# GNSS_OCXO.net
KiCad netlist of a schematic drawn in Altium Designer
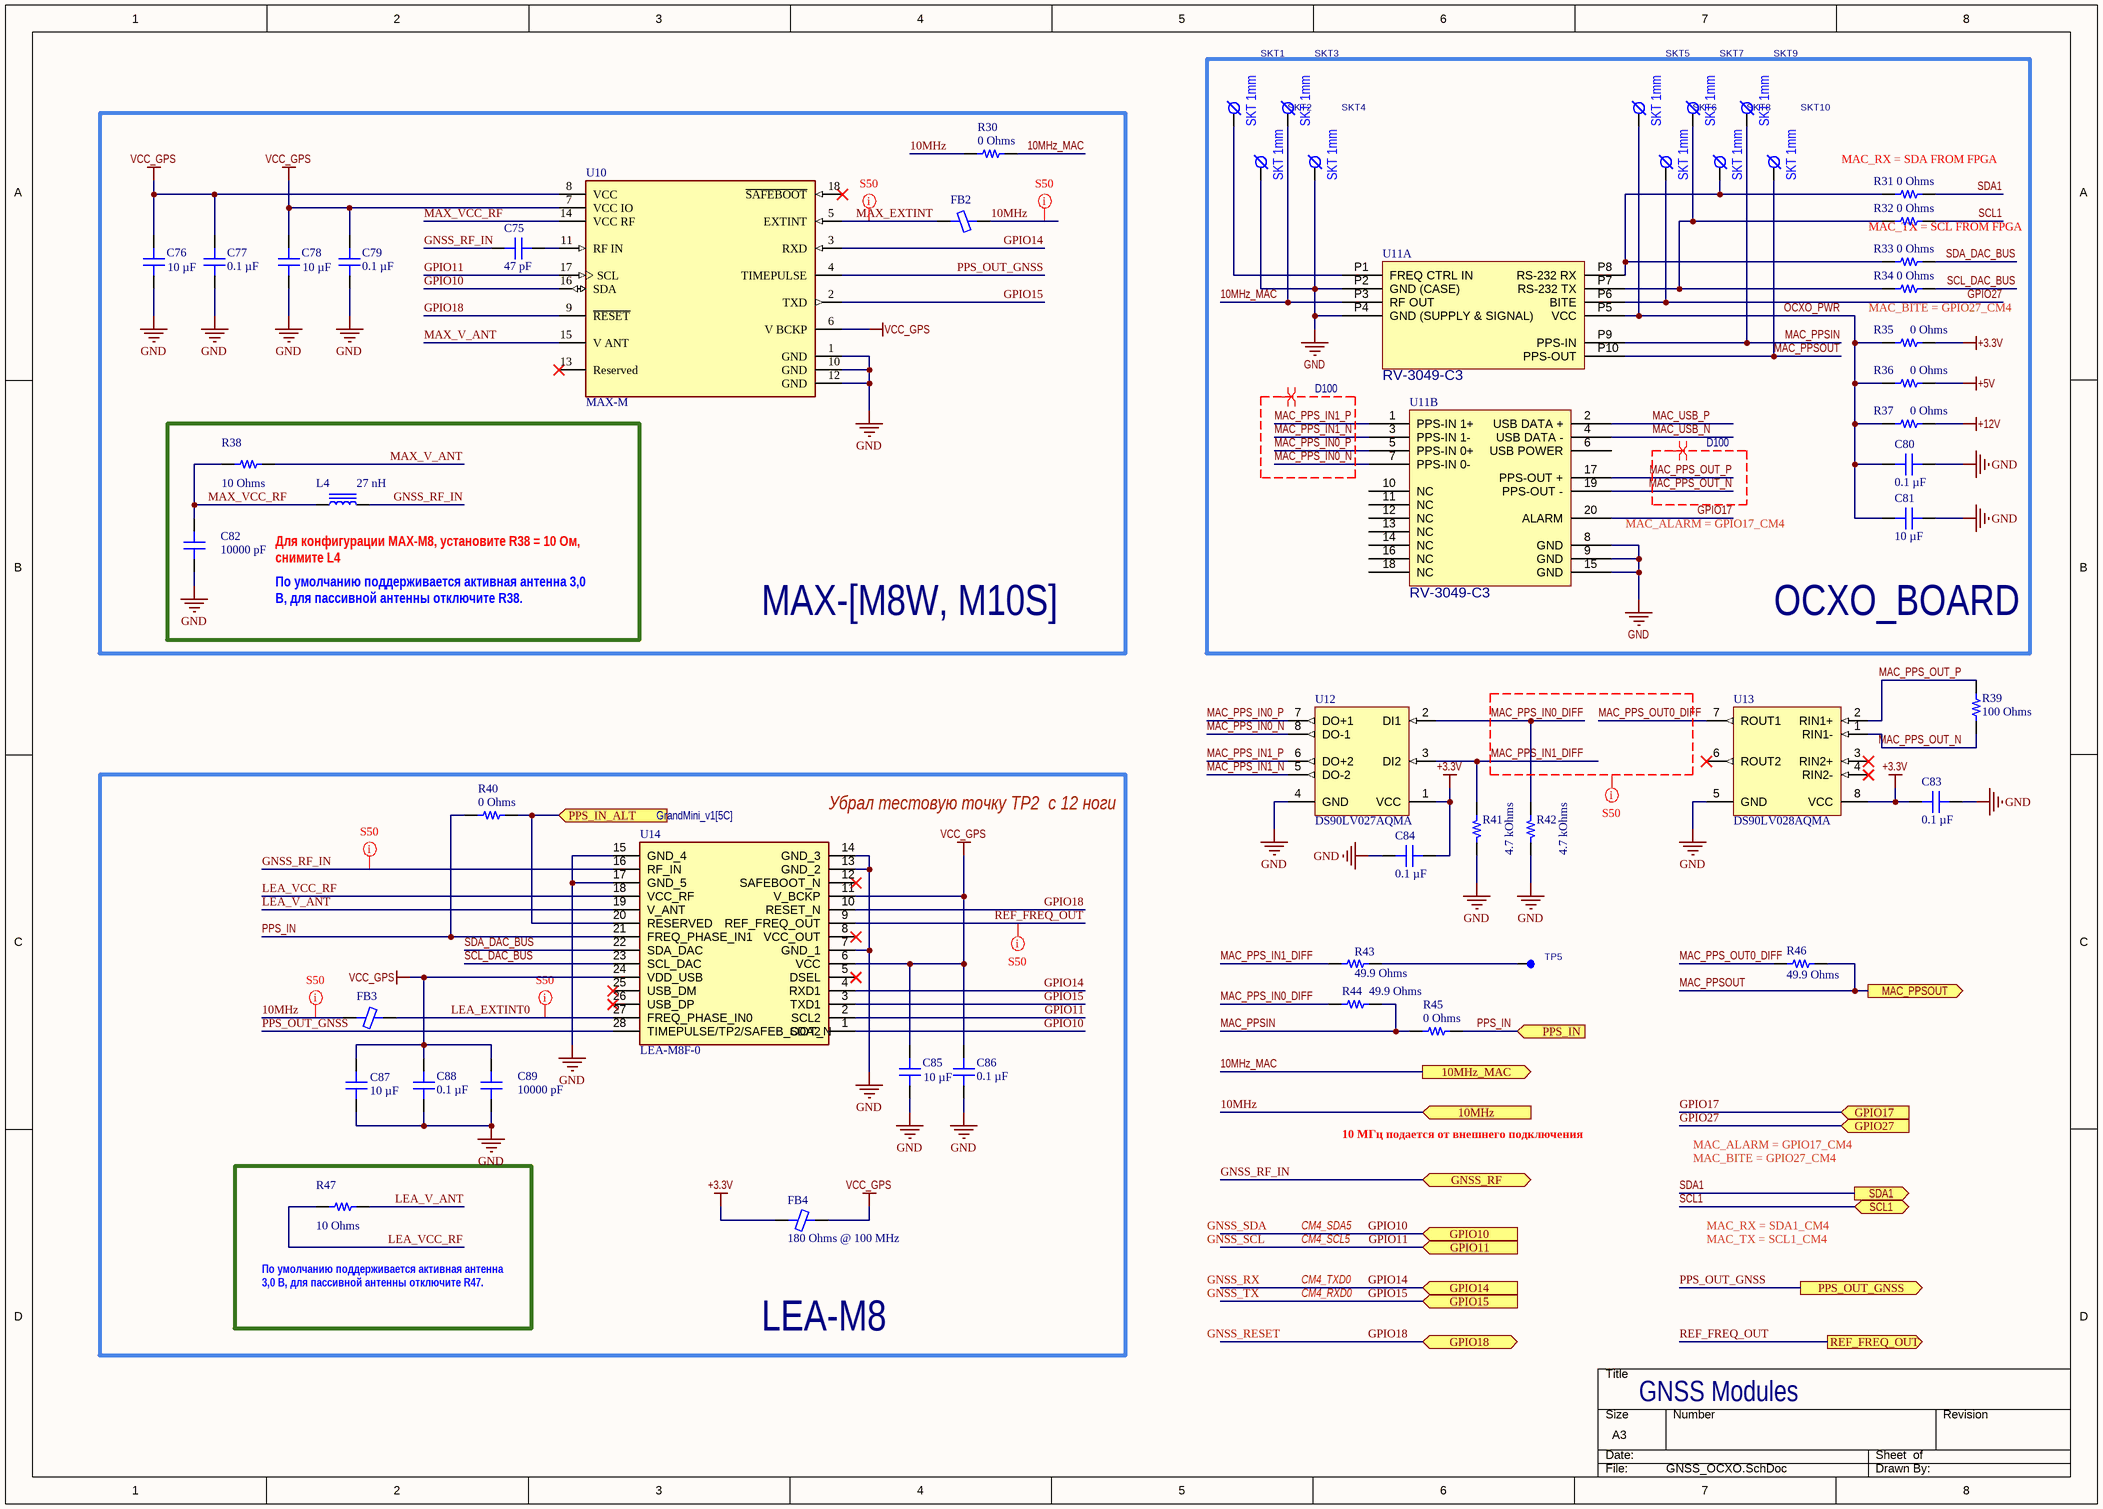
[diagram p0: GNSS_OCXO.SchDoc]

(export (version "E")
  (design (tool "Eeschema 10.0.6"))
  (components
    (comp (ref "C75")
      (value "47 pF")
      (footprint "CAP 0603_1608")
      (description "CAP CER 47PF 25V C0G/NPO 0603")
      (fields (field (name "MANUFACTURER") "Yageo") (field (name "TOLERANCE") "±5%"))
      (libsource (lib "Celestial Altium Library - altium_library") (part "Capacitor"))
    )
    (comp (ref "C76")
      (value "10 µF")
      (footprint "CAP 0805_2012")
      (description "CAP CER 10UF 25V X5R 0805")
      (fields
        (field (name "TOLERANCE") "±10%")
        (field (name "CAPACITANCE") "10 µF")
        (field (name "PART NUMBER") "CC0805KKX5R8BB106")
      )
      (libsource (lib "Celestial Altium Library - altium_library") (part "Capacitor"))
    )
    (comp (ref "C77")
      (value "0.1 µF")
      (footprint "CAP 0603_1608")
      (description "CAP CER 0.1UF 50V X7R 0603")
      (fields (field (name "MANUFACTURER") "Yageo") (field (name "TOLERANCE") "±10%"))
      (libsource (lib "Celestial Altium Library - altium_library") (part "Capacitor"))
    )
    (comp (ref "C78")
      (value "10 µF")
      (footprint "CAP 0805_2012")
      (description "CAP CER 10UF 25V X5R 0805")
      (fields
        (field (name "TOLERANCE") "±10%")
        (field (name "CAPACITANCE") "10 µF")
        (field (name "PART NUMBER") "CC0805KKX5R8BB106")
      )
      (libsource (lib "Celestial Altium Library - altium_library") (part "Capacitor"))
    )
    (comp (ref "C79")
      (value "0.1 µF")
      (footprint "CAP 0603_1608")
      (description "CAP CER 0.1UF 50V X7R 0603")
      (fields (field (name "MANUFACTURER") "Yageo") (field (name "TOLERANCE") "±10%"))
      (libsource (lib "Celestial Altium Library - altium_library") (part "Capacitor"))
    )
    (comp (ref "C80")
      (value "0.1 µF")
      (footprint "CAP 0603_1608")
      (description "CAP CER 0.1UF 50V X7R 0603")
      (fields (field (name "MANUFACTURER") "Yageo") (field (name "PART NUMBER") "CC0603KRX7R9BB104"))
      (libsource (lib "Celestial Altium Library - altium_library") (part "Capacitor"))
    )
    (comp (ref "C81")
      (value "10 µF")
      (footprint "CAP 0805_2012")
      (description "CAP CER 10UF 25V X5R 0805")
      (fields
        (field (name "TOLERANCE") "±10%")
        (field (name "CAPACITANCE") "10 µF")
        (field (name "PART NUMBER") "CC0805KKX5R8BB106")
      )
      (libsource (lib "Celestial Altium Library - altium_library") (part "Capacitor"))
    )
    (comp (ref "C82")
      (value "10000 pF")
      (footprint "CAP 0603_1608")
      (description "CAP CER 10000PF 50V X7R 0603")
      (fields (field (name "MANUFACTURER") "Yageo") (field (name "PART NUMBER") "CC0603KRX7R9BB103"))
      (libsource (lib "Celestial Altium Library - altium_library") (part "Capacitor"))
    )
    (comp (ref "C83")
      (value "0.1 µF")
      (footprint "CAP 0603_1608")
      (description "CAP CER 0.1UF 50V X7R 0603")
      (fields (field (name "MANUFACTURER") "Yageo") (field (name "PART NUMBER") "CC0603KRX7R9BB104"))
      (libsource (lib "Celestial Altium Library - altium_library") (part "Capacitor"))
    )
    (comp (ref "C84")
      (value "0.1 µF")
      (footprint "CAP 0603_1608")
      (description "CAP CER 0.1UF 50V X7R 0603")
      (fields (field (name "MANUFACTURER") "Yageo") (field (name "PART NUMBER") "CC0603KRX7R9BB104"))
      (libsource (lib "Celestial Altium Library - altium_library") (part "Capacitor"))
    )
    (comp (ref "C85")
      (value "10 µF")
      (footprint "CAP 0805_2012")
      (description "CAP CER 10UF 25V X5R 0805")
      (fields
        (field (name "TOLERANCE") "±10%")
        (field (name "CAPACITANCE") "10 µF")
        (field (name "PART NUMBER") "CC0805KKX5R8BB106")
      )
      (libsource (lib "Celestial Altium Library - altium_library") (part "Capacitor"))
    )
    (comp (ref "C86")
      (value "0.1 µF")
      (footprint "CAP 0603_1608")
      (description "CAP CER 0.1UF 50V X7R 0603")
      (fields (field (name "MANUFACTURER") "Yageo") (field (name "TOLERANCE") "±10%"))
      (libsource (lib "Celestial Altium Library - altium_library") (part "Capacitor"))
    )
    (comp (ref "C87")
      (value "10 µF")
      (footprint "CAP 0805_2012")
      (description "CAP CER 10UF 25V X5R 0805")
      (fields
        (field (name "TOLERANCE") "±10%")
        (field (name "CAPACITANCE") "10 µF")
        (field (name "PART NUMBER") "CC0805KKX5R8BB106")
      )
      (libsource (lib "Celestial Altium Library - altium_library") (part "Capacitor"))
    )
    (comp (ref "C88")
      (value "0.1 µF")
      (footprint "CAP 0603_1608")
      (description "CAP CER 0.1UF 50V X7R 0603")
      (fields (field (name "MANUFACTURER") "Yageo") (field (name "TOLERANCE") "±10%"))
      (libsource (lib "Celestial Altium Library - altium_library") (part "Capacitor"))
    )
    (comp (ref "C89")
      (value "10000 pF")
      (footprint "CAP 0603_1608")
      (description "CAP CER 10000PF 50V X7R 0603")
      (fields (field (name "MANUFACTURER") "Yageo") (field (name "PART NUMBER") "CC0603KRX7R9BB103"))
      (libsource (lib "Celestial Altium Library - altium_library") (part "Capacitor"))
    )
    (comp (ref "FB2")
      (value "1 kOhms @ 100 MHz")
      (footprint "FER 0603_1608")
      (description "FERRITE BEAD 1K OHM 0603 1LN")
      (fields
        (field (name "PART NUMBER") "BLM18HG102SH1D")
        (field (name "MANUFACTURER") "Murata Electronics")
      )
      (libsource (lib "Celestial Altium Library - altium_library") (part "Ferrite Chip"))
    )
    (comp (ref "FB3")
      (value "1 kOhms @ 100 MHz")
      (footprint "FER 0603_1608")
      (description "FERRITE BEAD 1K OHM 0603 1LN")
      (fields
        (field (name "PART NUMBER") "BLM18HG102SH1D")
        (field (name "MANUFACTURER") "Murata Electronics")
      )
      (libsource (lib "Celestial Altium Library - altium_library") (part "Ferrite Chip"))
    )
    (comp (ref "FB4")
      (value "180 Ohms @ 100 MHz")
      (footprint "FER 0603_1608")
      (description "FERRITE BEAD 180 OHM 0603 1LN")
      (fields
        (field (name "PART NUMBER") "BLM18PG181SN1D")
        (field (name "MANUFACTURER") "Murata Electronics")
      )
      (libsource (lib "Celestial Altium Library - altium_library") (part "Ferrite Chip"))
    )
    (comp (ref "L4")
      (value "27 nH")
      (footprint "Murata LQW18 0603")
      (description "FIXED IND 27NH 440MA 0.21OHM SMD")
      (fields (field (name "TOLERANCE") "±2%") (field (name "PART NUMBER") "LQW18AN27NG00D"))
      (libsource (lib "Celestial Altium Library - altium_library") (part "Inductor"))
    )
    (comp (ref "R30")
      (value "0 Ohms")
      (footprint "YAGEO RES 0603_1608")
      (description "RES 0 OHM JUMPER 1/10W 0603")
      (fields (field (name "TOLERANCE") "Jumper") (field (name "MANUFACTURER") "Yageo"))
      (libsource (lib "Celestial Altium Library - altium_library") (part "Resistor"))
    )
    (comp (ref "R31")
      (value "0 Ohms")
      (footprint "YAGEO RES 0603_1608")
      (description "RES 0 OHM JUMPER 1/10W 0603")
      (fields (field (name "PART NUMBER") "RC0603FR-070RL") (field (name "MANUFACTURER") "Yageo"))
      (libsource (lib "Celestial Altium Library - altium_library") (part "Resistor"))
    )
    (comp (ref "R32")
      (value "0 Ohms")
      (footprint "YAGEO RES 0603_1608")
      (description "RES 0 OHM JUMPER 1/10W 0603")
      (fields (field (name "PART NUMBER") "RC0603FR-070RL") (field (name "MANUFACTURER") "Yageo"))
      (libsource (lib "Celestial Altium Library - altium_library") (part "Resistor"))
    )
    (comp (ref "R33")
      (value "0 Ohms")
      (footprint "YAGEO RES 0603_1608")
      (description "RES 0 OHM JUMPER 1/10W 0603")
      (fields (field (name "PART NUMBER") "RC0603FR-070RL") (field (name "MANUFACTURER") "Yageo"))
      (libsource (lib "Celestial Altium Library - altium_library") (part "Resistor"))
    )
    (comp (ref "R34")
      (value "0 Ohms")
      (footprint "YAGEO RES 0603_1608")
      (description "RES 0 OHM JUMPER 1/10W 0603")
      (fields (field (name "PART NUMBER") "RC0603FR-070RL") (field (name "MANUFACTURER") "Yageo"))
      (libsource (lib "Celestial Altium Library - altium_library") (part "Resistor"))
    )
    (comp (ref "R35")
      (value "0 Ohms")
      (footprint "YAGEO RES 0603_1608")
      (description "RES 0 OHM JUMPER 1/10W 0603")
      (fields (field (name "PART NUMBER") "RC0603FR-070RL") (field (name "MANUFACTURER") "Yageo"))
      (libsource (lib "Celestial Altium Library - altium_library") (part "Resistor"))
    )
    (comp (ref "R36")
      (value "0 Ohms")
      (footprint "YAGEO RES 0603_1608")
      (description "RES 0 OHM JUMPER 1/10W 0603")
      (fields (field (name "PART NUMBER") "RC0603FR-070RL") (field (name "MANUFACTURER") "Yageo"))
      (libsource (lib "Celestial Altium Library - altium_library") (part "Resistor"))
    )
    (comp (ref "R37")
      (value "0 Ohms")
      (footprint "YAGEO RES 0603_1608")
      (description "RES 0 OHM JUMPER 1/10W 0603")
      (fields (field (name "PART NUMBER") "RC0603FR-070RL") (field (name "MANUFACTURER") "Yageo"))
      (libsource (lib "Celestial Altium Library - altium_library") (part "Resistor"))
    )
    (comp (ref "R38")
      (value "10 Ohms")
      (footprint "YAGEO RES 0603_1608")
      (description "RES 10 OHM 1% 1/10W 0603")
      (fields (field (name "MANUFACTURER") "Yageo") (field (name "TOLERANCE") "±1%"))
      (libsource (lib "Celestial Altium Library - altium_library") (part "Resistor"))
    )
    (comp (ref "R39")
      (value "100 Ohms")
      (footprint "YAGEO RES 0603_1608")
      (description "RES 100 OHM 1% 1/10W 0603")
      (fields (field (name "PART NUMBER") "RC0603FR-07100RL") (field (name "MANUFACTURER") "Yageo"))
      (libsource (lib "Celestial Altium Library - altium_library") (part "Resistor"))
    )
    (comp (ref "R40")
      (value "0 Ohms")
      (footprint "YAGEO RES 0603_1608")
      (description "RES 0 OHM JUMPER 1/10W 0603")
      (fields (field (name "TOLERANCE") "Jumper") (field (name "MANUFACTURER") "Yageo"))
      (libsource (lib "Celestial Altium Library - altium_library") (part "Resistor"))
    )
    (comp (ref "R41")
      (value "4.7 kOhms")
      (footprint "YAGEO RES 0402_1005")
      (description "RES 4.7K OHM 1% 1/16W 0402")
      (fields (field (name "MANUFACTURER") "Yageo") (field (name "TOLERANCE") "±1%"))
      (libsource (lib "Celestial Altium Library - altium_library") (part "Resistor"))
    )
    (comp (ref "R42")
      (value "4.7 kOhms")
      (footprint "YAGEO RES 0402_1005")
      (description "RES 4.7K OHM 1% 1/16W 0402")
      (fields (field (name "MANUFACTURER") "Yageo") (field (name "TOLERANCE") "±1%"))
      (libsource (lib "Celestial Altium Library - altium_library") (part "Resistor"))
    )
    (comp (ref "R43")
      (value "49.9 Ohms")
      (footprint "YAGEO RES 0603_1608")
      (description "RES 49.9 OHM 1% 1/10W 0603")
      (fields (field (name "PART NUMBER") "RC0603FR-0749R9L") (field (name "MANUFACTURER") "Yageo"))
      (libsource (lib "Celestial Altium Library - altium_library") (part "Resistor"))
    )
    (comp (ref "R44")
      (value "49.9 Ohms")
      (footprint "YAGEO RES 0603_1608")
      (description "RES 49.9 OHM 1% 1/10W 0603")
      (fields (field (name "PART NUMBER") "RC0603FR-0749R9L") (field (name "MANUFACTURER") "Yageo"))
      (libsource (lib "Celestial Altium Library - altium_library") (part "Resistor"))
    )
    (comp (ref "R45")
      (value "0 Ohms")
      (footprint "YAGEO RES 0603_1608")
      (description "RES 0 OHM JUMPER 1/10W 0603")
      (fields (field (name "TOLERANCE") "Jumper") (field (name "MANUFACTURER") "Yageo"))
      (libsource (lib "Celestial Altium Library - altium_library") (part "Resistor"))
    )
    (comp (ref "R46")
      (value "49.9 Ohms")
      (footprint "YAGEO RES 0603_1608")
      (description "RES 49.9 OHM 1% 1/10W 0603")
      (fields (field (name "PART NUMBER") "RC0603FR-0749R9L") (field (name "MANUFACTURER") "Yageo"))
      (libsource (lib "Celestial Altium Library - altium_library") (part "Resistor"))
    )
    (comp (ref "R47")
      (value "10 Ohms")
      (footprint "YAGEO RES 0603_1608")
      (description "RES 10 OHM 1% 1/10W 0603")
      (fields (field (name "MANUFACTURER") "Yageo") (field (name "TOLERANCE") "±1%"))
      (libsource (lib "Celestial Altium Library - altium_library") (part "Resistor"))
    )
    (comp (ref "SKT1")
      (value "SKT plug")
      (footprint "SamacSys:0332-0-43-80-18-27-10-0")
      (description "PCB OFP SLDR MT RECPT #18 CNTCT .037-.043")
      (fields (field (name "MANUFACTURER") "Mill-Max"))
      (libsource (lib "SamacSys") (part "0332-0-43-80-18-27-10-0"))
    )
    (comp (ref "SKT2")
      (value "SKT plug")
      (footprint "SamacSys:0332-0-43-80-18-27-10-0")
      (description "PCB OFP SLDR MT RECPT #18 CNTCT .037-.043")
      (fields (field (name "MANUFACTURER") "Mill-Max"))
      (libsource (lib "SamacSys") (part "0332-0-43-80-18-27-10-0"))
    )
    (comp (ref "SKT3")
      (value "SKT plug")
      (footprint "SamacSys:0332-0-43-80-18-27-10-0")
      (description "PCB OFP SLDR MT RECPT #18 CNTCT .037-.043")
      (fields (field (name "MANUFACTURER") "Mill-Max"))
      (libsource (lib "SamacSys") (part "0332-0-43-80-18-27-10-0"))
    )
    (comp (ref "SKT4")
      (value "SKT plug")
      (footprint "SamacSys:0332-0-43-80-18-27-10-0")
      (description "PCB OFP SLDR MT RECPT #18 CNTCT .037-.043")
      (fields (field (name "MANUFACTURER") "Mill-Max"))
      (libsource (lib "SamacSys") (part "0332-0-43-80-18-27-10-0"))
    )
    (comp (ref "SKT5")
      (value "SKT plug")
      (footprint "SamacSys:0332-0-43-80-18-27-10-0")
      (description "PCB OFP SLDR MT RECPT #18 CNTCT .037-.043")
      (fields (field (name "MANUFACTURER") "Mill-Max"))
      (libsource (lib "SamacSys") (part "0332-0-43-80-18-27-10-0"))
    )
    (comp (ref "SKT6")
      (value "SKT plug")
      (footprint "SamacSys:0332-0-43-80-18-27-10-0")
      (description "PCB OFP SLDR MT RECPT #18 CNTCT .037-.043")
      (fields (field (name "MANUFACTURER") "Mill-Max"))
      (libsource (lib "SamacSys") (part "0332-0-43-80-18-27-10-0"))
    )
    (comp (ref "SKT7")
      (value "SKT plug")
      (footprint "SamacSys:0332-0-43-80-18-27-10-0")
      (description "PCB OFP SLDR MT RECPT #18 CNTCT .037-.043")
      (fields (field (name "MANUFACTURER") "Mill-Max"))
      (libsource (lib "SamacSys") (part "0332-0-43-80-18-27-10-0"))
    )
    (comp (ref "SKT8")
      (value "SKT plug")
      (footprint "SamacSys:0332-0-43-80-18-27-10-0")
      (description "PCB OFP SLDR MT RECPT #18 CNTCT .037-.043")
      (fields (field (name "MANUFACTURER") "Mill-Max"))
      (libsource (lib "SamacSys") (part "0332-0-43-80-18-27-10-0"))
    )
    (comp (ref "SKT9")
      (value "SKT plug")
      (footprint "SamacSys:0332-0-43-80-18-27-10-0")
      (description "PCB OFP SLDR MT RECPT #18 CNTCT .037-.043")
      (fields (field (name "MANUFACTURER") "Mill-Max"))
      (libsource (lib "SamacSys") (part "0332-0-43-80-18-27-10-0"))
    )
    (comp (ref "SKT10")
      (value "SKT plug")
      (footprint "SamacSys:0332-0-43-80-18-27-10-0")
      (description "PCB OFP SLDR MT RECPT #18 CNTCT .037-.043")
      (fields (field (name "MANUFACTURER") "Mill-Max"))
      (libsource (lib "SamacSys") (part "0332-0-43-80-18-27-10-0"))
    )
    (comp (ref "TP5")
      (value "PAD_TEST")
      (footprint "Samacsys:PAD_TEST")
      (description "Test Point")
      (fields (field (name "TOLERANCE") "{Tolerance}") (field (name "MANUFACTURER") "{Manufacturer}"))
      (libsource (lib "SamacSys") (part "PAD_TEST"))
    )
    (comp (ref "U10")
      (value "MAX-M")
      (footprint "FP-MAX-M8W-0-MFG")
      (description "RF RCVR GNSS/GPS 1.575GHZ 18LCC")
      (libsource (lib "Altium Content Vault") (part "36e94f557bbf38d877319147cff7e99"))
    )
    (comp (ref "U11")
      (value "RV-3049-C3")
      (footprint "OCXO_CARD")
      (description "MOD, MAC, MAC-SA5X, ATOMIC CLOCK")
      (fields (field (name "MFG PART NUM") "MAC-SA5X") (field (name "VELENTIUM PART NUM") "<V PART NUM>"))
      (libsource (lib "SHIWA_lib") (part "MAC-SA5X"))
    )
    (comp (ref "U12")
      (value "DS90LV027AQMA")
      (footprint "M08A_N")
      (description "Automotive LVDS Dual Differential Driver, 8-pin Narrow SOIC")
      (fields (field (name "MANUFACTURER") "National Semiconductor"))
      (libsource (lib "Altium Content Vault") (part "IN-LNDRV-DS90LV027AHM"))
    )
    (comp (ref "U13")
      (value "DS90LV028AQMA")
      (footprint "M08A_L")
      (description "Automotive LVDS Dual Differential Line Receiver, 8-pin Narrow SOIC")
      (fields (field (name "MANUFACTURER") "National Semiconductor"))
      (libsource (lib "Altium Content Vault") (part "IN-LNRX-DS90LV028AHM"))
    )
    (comp (ref "U14")
      (value "LEA-M8F-0")
      (footprint "SamacSys:LEAM8F0")
      (description "Integrated Circuit")
      (fields (field (name "MOUSER PART NUMBER") "377-LEA-M8F-0"))
      (libsource (lib "SamacSys") (part "LEA-M8F-0"))
    )
  )
  (nets
    (net (code "1") (name "+3.3V") (class "Default")
      (node (ref "C83") (pin "1") (pinfunction "1_1") (pintype "passive"))
      (node (ref "C84") (pin "2") (pinfunction "2_2") (pintype "passive"))
      (node (ref "FB4") (pin "1") (pinfunction "1_1") (pintype "passive"))
      (node (ref "R35") (pin "1") (pinfunction "1_1") (pintype "passive"))
      (node (ref "U12") (pin "1") (pinfunction "VCC_1") (pintype "power_in"))
      (node (ref "U13") (pin "8") (pinfunction "VCC_8") (pintype "power_in"))
    )
    (net (code "2") (name "+5V") (class "Default")
      (node (ref "R36") (pin "1") (pinfunction "1_1") (pintype "passive"))
    )
    (net (code "3") (name "+12V") (class "Default")
      (node (ref "R37") (pin "1") (pinfunction "1_1") (pintype "passive"))
    )
    (net (code "4") (name "/10MHz") (class "Default")
      (node (ref "FB2") (pin "1") (pinfunction "1_1") (pintype "passive"))
      (node (ref "FB3") (pin "1") (pinfunction "1_1") (pintype "passive"))
      (node (ref "R30") (pin "1") (pinfunction "1_1") (pintype "passive"))
    )
    (net (code "5") (name "/10MHz_MAC") (class "Default")
      (node (ref "R30") (pin "2") (pinfunction "2_2") (pintype "passive"))
      (node (ref "SKT3") (pin "1") (pinfunction "1_1") (pintype "passive"))
      (node (ref "U11") (pin "P3") (pinfunction "RF_OUT_P3") (pintype "passive"))
    )
    (net (code "6") (name "/GNSS_RF_IN") (class "Default")
      (node (ref "C75") (pin "1") (pinfunction "1_1") (pintype "passive"))
      (node (ref "L4") (pin "2") (pinfunction "2_2") (pintype "passive"))
      (node (ref "U14") (pin "16") (pinfunction "RF_IN_16") (pintype "passive"))
    )
    (net (code "7") (name "/GPIO10") (class "Default")
      (node (ref "U10") (pin "16") (pinfunction "SDA_16") (pintype "bidirectional"))
      (node (ref "U14") (pin "1") (pinfunction "SDA2_1") (pintype "passive"))
    )
    (net (code "8") (name "/GPIO11") (class "Default")
      (node (ref "U10") (pin "17") (pinfunction "SCL_17") (pintype "input"))
      (node (ref "U14") (pin "2") (pinfunction "SCL2_2") (pintype "passive"))
    )
    (net (code "9") (name "/GPIO14") (class "Default")
      (node (ref "U10") (pin "3") (pinfunction "RXD_3") (pintype "input"))
      (node (ref "U14") (pin "4") (pinfunction "RXD1_4") (pintype "passive"))
    )
    (net (code "10") (name "/GPIO15") (class "Default")
      (node (ref "U10") (pin "2") (pinfunction "TXD_2") (pintype "output"))
      (node (ref "U14") (pin "3") (pinfunction "TXD1_3") (pintype "passive"))
    )
    (net (code "11") (name "/GPIO17") (class "Default")
      (node (ref "U11") (pin "20") (pinfunction "ALARM_20") (pintype "passive"))
    )
    (net (code "12") (name "/GPIO18") (class "Default")
      (node (ref "U10") (pin "9") (pinfunction "~{RESET}_9") (pintype "passive"))
      (node (ref "U14") (pin "10") (pinfunction "RESET_N_10") (pintype "passive"))
    )
    (net (code "13") (name "/GPIO27") (class "Default")
      (node (ref "SKT6") (pin "1") (pinfunction "1_1") (pintype "passive"))
      (node (ref "U11") (pin "P6") (pinfunction "BITE_P6") (pintype "passive"))
    )
    (net (code "14") (name "/LEA_EXTINT0") (class "Default")
      (node (ref "FB3") (pin "2") (pinfunction "2_2") (pintype "passive"))
      (node (ref "U14") (pin "27") (pinfunction "FREQ_PHASE_IN0_27") (pintype "passive"))
    )
    (net (code "15") (name "/LEA_VCC_RF") (class "Default")
      (node (ref "R47") (pin "1") (pinfunction "1_1") (pintype "passive"))
      (node (ref "U14") (pin "18") (pinfunction "VCC_RF_18") (pintype "passive"))
    )
    (net (code "16") (name "/LEA_V_ANT") (class "Default")
      (node (ref "R47") (pin "2") (pinfunction "2_2") (pintype "passive"))
      (node (ref "U14") (pin "19") (pinfunction "V_ANT_19") (pintype "passive"))
    )
    (net (code "17") (name "/MAC_PPSIN") (class "Default")
      (node (ref "R44") (pin "2") (pinfunction "2_2") (pintype "passive"))
      (node (ref "R45") (pin "1") (pinfunction "1_1") (pintype "passive"))
      (node (ref "SKT9") (pin "1") (pinfunction "1_1") (pintype "passive"))
      (node (ref "U11") (pin "P9") (pinfunction "PPS-IN_P9") (pintype "passive"))
    )
    (net (code "18") (name "/MAC_PPSOUT") (class "Default")
      (node (ref "R46") (pin "2") (pinfunction "2_2") (pintype "passive"))
      (node (ref "SKT10") (pin "1") (pinfunction "1_1") (pintype "passive"))
      (node (ref "U11") (pin "P10") (pinfunction "PPS-OUT_P10") (pintype "passive"))
    )
    (net (code "19") (name "/MAC_PPS_IN0_DIFF") (class "Default")
      (node (ref "R42") (pin "2") (pinfunction "2_2") (pintype "passive"))
      (node (ref "R44") (pin "1") (pinfunction "1_1") (pintype "passive"))
      (node (ref "U12") (pin "2") (pinfunction "DI1_2") (pintype "input"))
    )
    (net (code "20") (name "/MAC_PPS_IN0_N") (class "Default")
      (node (ref "U11") (pin "7") (pinfunction "PPS-IN_0-_7") (pintype "passive"))
      (node (ref "U12") (pin "8") (pinfunction "DO-1_8") (pintype "output"))
    )
    (net (code "21") (name "/MAC_PPS_IN0_P") (class "Default")
      (node (ref "U11") (pin "5") (pinfunction "PPS-IN_0+_5") (pintype "passive"))
      (node (ref "U12") (pin "7") (pinfunction "DO+1_7") (pintype "output"))
    )
    (net (code "22") (name "/MAC_PPS_IN1_DIFF") (class "Default")
      (node (ref "R41") (pin "2") (pinfunction "2_2") (pintype "passive"))
      (node (ref "R43") (pin "1") (pinfunction "1_1") (pintype "passive"))
      (node (ref "U12") (pin "3") (pinfunction "DI2_3") (pintype "input"))
    )
    (net (code "23") (name "/MAC_PPS_IN1_N") (class "Default")
      (node (ref "U11") (pin "3") (pinfunction "PPS-IN_1-_3") (pintype "passive"))
      (node (ref "U12") (pin "5") (pinfunction "DO-2_5") (pintype "output"))
    )
    (net (code "24") (name "/MAC_PPS_IN1_P") (class "Default")
      (node (ref "U11") (pin "1") (pinfunction "PPS-IN_1+_1") (pintype "passive"))
      (node (ref "U12") (pin "6") (pinfunction "DO+2_6") (pintype "output"))
    )
    (net (code "25") (name "/MAC_PPS_OUT0_DIFF") (class "Default")
      (node (ref "R46") (pin "1") (pinfunction "1_1") (pintype "passive"))
      (node (ref "U13") (pin "7") (pinfunction "ROUT1_7") (pintype "output"))
    )
    (net (code "26") (name "/MAC_PPS_OUT_N") (class "Default")
      (node (ref "R39") (pin "1") (pinfunction "1_1") (pintype "passive"))
      (node (ref "U11") (pin "19") (pinfunction "PPS-OUT_-_19") (pintype "passive"))
      (node (ref "U13") (pin "1") (pinfunction "RIN1-_1") (pintype "input"))
    )
    (net (code "27") (name "/MAC_PPS_OUT_P") (class "Default")
      (node (ref "R39") (pin "2") (pinfunction "2_2") (pintype "passive"))
      (node (ref "U11") (pin "17") (pinfunction "PPS-OUT_+_17") (pintype "passive"))
      (node (ref "U13") (pin "2") (pinfunction "RIN1+_2") (pintype "input"))
    )
    (net (code "28") (name "/MAC_USB_N") (class "Default")
      (node (ref "U11") (pin "4") (pinfunction "USB_DATA_-_4") (pintype "passive"))
    )
    (net (code "29") (name "/MAC_USB_P") (class "Default")
      (node (ref "U11") (pin "2") (pinfunction "USB_DATA_+_2") (pintype "passive"))
    )
    (net (code "30") (name "/MAX_EXTINT") (class "Default")
      (node (ref "FB2") (pin "2") (pinfunction "2_2") (pintype "passive"))
      (node (ref "U10") (pin "5") (pinfunction "EXTINT_5") (pintype "input"))
    )
    (net (code "31") (name "/MAX_VCC_RF") (class "Default")
      (node (ref "C82") (pin "2") (pinfunction "2_2") (pintype "passive"))
      (node (ref "L4") (pin "1") (pinfunction "1_1") (pintype "passive"))
      (node (ref "R38") (pin "1") (pinfunction "1_1") (pintype "passive"))
      (node (ref "U10") (pin "14") (pinfunction "VCC_RF_14") (pintype "power_in"))
    )
    (net (code "32") (name "/MAX_V_ANT") (class "Default")
      (node (ref "R38") (pin "2") (pinfunction "2_2") (pintype "passive"))
      (node (ref "U10") (pin "15") (pinfunction "V_ANT_15") (pintype "power_in"))
    )
    (net (code "33") (name "/OCXO_PWR") (class "Default")
      (node (ref "C80") (pin "1") (pinfunction "1_1") (pintype "passive"))
      (node (ref "C81") (pin "2") (pinfunction "2_2") (pintype "passive"))
      (node (ref "R35") (pin "2") (pinfunction "2_2") (pintype "passive"))
      (node (ref "R36") (pin "2") (pinfunction "2_2") (pintype "passive"))
      (node (ref "R37") (pin "2") (pinfunction "2_2") (pintype "passive"))
      (node (ref "SKT5") (pin "1") (pinfunction "1_1") (pintype "passive"))
      (node (ref "U11") (pin "P5") (pinfunction "VCC_P5") (pintype "passive"))
    )
    (net (code "34") (name "/PPS_IN") (class "Default")
      (node (ref "R40") (pin "1") (pinfunction "1_1") (pintype "passive"))
      (node (ref "R45") (pin "2") (pinfunction "2_2") (pintype "passive"))
      (node (ref "U14") (pin "21") (pinfunction "FREQ_PHASE_IN1_21") (pintype "passive"))
    )
    (net (code "35") (name "/PPS_IN_ALT") (class "Default")
      (node (ref "R40") (pin "2") (pinfunction "2_2") (pintype "passive"))
      (node (ref "U14") (pin "20") (pinfunction "RESERVED_20") (pintype "passive"))
    )
    (net (code "36") (name "/PPS_OUT_GNSS") (class "Default")
      (node (ref "U10") (pin "4") (pinfunction "TIMEPULSE_4") (pintype "passive"))
      (node (ref "U14") (pin "28") (pinfunction "TIMEPULSE/TP2/SAFEB_OOT_N_28") (pintype "passive"))
    )
    (net (code "37") (name "/REF_FREQ_OUT") (class "Default")
      (node (ref "U14") (pin "9") (pinfunction "REF_FREQ_OUT_9") (pintype "passive"))
    )
    (net (code "38") (name "/SCL1") (class "Default")
      (node (ref "R32") (pin "1") (pinfunction "1_1") (pintype "passive"))
    )
    (net (code "39") (name "/SCL_DAC_BUS") (class "Default")
      (node (ref "R34") (pin "1") (pinfunction "1_1") (pintype "passive"))
      (node (ref "U14") (pin "23") (pinfunction "SCL_DAC_23") (pintype "passive"))
    )
    (net (code "40") (name "/SDA1") (class "Default")
      (node (ref "R31") (pin "1") (pinfunction "1_1") (pintype "passive"))
    )
    (net (code "41") (name "/SDA_DAC_BUS") (class "Default")
      (node (ref "R33") (pin "1") (pinfunction "1_1") (pintype "passive"))
      (node (ref "U14") (pin "22") (pinfunction "SDA_DAC_22") (pintype "passive"))
    )
    (net (code "42") (name "GND") (class "Default")
      (node (ref "C76") (pin "1") (pinfunction "1_1") (pintype "passive"))
      (node (ref "C77") (pin "1") (pinfunction "1_1") (pintype "passive"))
      (node (ref "C78") (pin "1") (pinfunction "1_1") (pintype "passive"))
      (node (ref "C79") (pin "1") (pinfunction "1_1") (pintype "passive"))
      (node (ref "C80") (pin "2") (pinfunction "2_2") (pintype "passive"))
      (node (ref "C81") (pin "1") (pinfunction "1_1") (pintype "passive"))
      (node (ref "C82") (pin "1") (pinfunction "1_1") (pintype "passive"))
      (node (ref "C83") (pin "2") (pinfunction "2_2") (pintype "passive"))
      (node (ref "C84") (pin "1") (pinfunction "1_1") (pintype "passive"))
      (node (ref "C85") (pin "1") (pinfunction "1_1") (pintype "passive"))
      (node (ref "C86") (pin "1") (pinfunction "1_1") (pintype "passive"))
      (node (ref "C87") (pin "1") (pinfunction "1_1") (pintype "passive"))
      (node (ref "C88") (pin "1") (pinfunction "1_1") (pintype "passive"))
      (node (ref "C89") (pin "1") (pinfunction "1_1") (pintype "passive"))
      (node (ref "R41") (pin "1") (pinfunction "1_1") (pintype "passive"))
      (node (ref "R42") (pin "1") (pinfunction "1_1") (pintype "passive"))
      (node (ref "SKT2") (pin "1") (pinfunction "1_1") (pintype "passive"))
      (node (ref "SKT4") (pin "1") (pinfunction "1_1") (pintype "passive"))
      (node (ref "U10") (pin "1") (pinfunction "GND_1") (pintype "power_in"))
      (node (ref "U10") (pin "10") (pinfunction "GND_10") (pintype "power_in"))
      (node (ref "U10") (pin "12") (pinfunction "GND_12") (pintype "power_in"))
      (node (ref "U11") (pin "15") (pinfunction "GND_15") (pintype "passive"))
      (node (ref "U11") (pin "8") (pinfunction "GND_8") (pintype "passive"))
      (node (ref "U11") (pin "9") (pinfunction "GND_9") (pintype "passive"))
      (node (ref "U11") (pin "P2") (pinfunction "GND_(CASE)_P2") (pintype "passive"))
      (node (ref "U11") (pin "P4") (pinfunction "GND_(SUPPLY_&_SIGNAL)_P4") (pintype "passive"))
      (node (ref "U12") (pin "4") (pinfunction "GND_4") (pintype "power_in"))
      (node (ref "U13") (pin "5") (pinfunction "GND_5") (pintype "power_in"))
      (node (ref "U14") (pin "13") (pinfunction "GND_2_13") (pintype "passive"))
      (node (ref "U14") (pin "14") (pinfunction "GND_3_14") (pintype "passive"))
      (node (ref "U14") (pin "15") (pinfunction "GND_4_15") (pintype "passive"))
      (node (ref "U14") (pin "17") (pinfunction "GND_5_17") (pintype "passive"))
      (node (ref "U14") (pin "7") (pinfunction "GND_1_7") (pintype "passive"))
    )
    (net (code "43") (name "Net-(R43-Pad2)") (class "Default")
      (node (ref "R43") (pin "2") (pinfunction "2_2") (pintype "passive"))
      (node (ref "TP5") (pin "1") (pinfunction "1_1") (pintype "passive"))
    )
    (net (code "44") (name "Net-(U10-RF_IN)") (class "Default")
      (node (ref "C75") (pin "2") (pinfunction "2_2") (pintype "passive"))
      (node (ref "U10") (pin "11") (pinfunction "RF_IN_11") (pintype "input"))
    )
    (net (code "45") (name "Net-(U11A-FREQ_CTRL_IN)") (class "Default")
      (node (ref "SKT1") (pin "1") (pinfunction "1_1") (pintype "passive"))
      (node (ref "U11") (pin "P1") (pinfunction "FREQ_CTRL_IN_P1") (pintype "passive"))
    )
    (net (code "46") (name "Net-(U11A-RS-232_RX)") (class "Default")
      (node (ref "R31") (pin "2") (pinfunction "2_2") (pintype "passive"))
      (node (ref "R33") (pin "2") (pinfunction "2_2") (pintype "passive"))
      (node (ref "SKT8") (pin "1") (pinfunction "1_1") (pintype "passive"))
      (node (ref "U11") (pin "P8") (pinfunction "RS-232_RX_P8") (pintype "passive"))
    )
    (net (code "47") (name "Net-(U11A-RS-232_TX)") (class "Default")
      (node (ref "R32") (pin "2") (pinfunction "2_2") (pintype "passive"))
      (node (ref "R34") (pin "2") (pinfunction "2_2") (pintype "passive"))
      (node (ref "SKT7") (pin "1") (pinfunction "1_1") (pintype "passive"))
      (node (ref "U11") (pin "P7") (pinfunction "RS-232_TX_P7") (pintype "passive"))
    )
    (net (code "48") (name "VCC_GPS") (class "Default")
      (node (ref "C76") (pin "2") (pinfunction "2_2") (pintype "passive"))
      (node (ref "C77") (pin "2") (pinfunction "2_2") (pintype "passive"))
      (node (ref "C78") (pin "2") (pinfunction "2_2") (pintype "passive"))
      (node (ref "C79") (pin "2") (pinfunction "2_2") (pintype "passive"))
      (node (ref "C85") (pin "2") (pinfunction "2_2") (pintype "passive"))
      (node (ref "C86") (pin "2") (pinfunction "2_2") (pintype "passive"))
      (node (ref "C87") (pin "2") (pinfunction "2_2") (pintype "passive"))
      (node (ref "C88") (pin "2") (pinfunction "2_2") (pintype "passive"))
      (node (ref "C89") (pin "2") (pinfunction "2_2") (pintype "passive"))
      (node (ref "FB4") (pin "2") (pinfunction "2_2") (pintype "passive"))
      (node (ref "U10") (pin "6") (pinfunction "V_BCKP_6") (pintype "power_in"))
      (node (ref "U10") (pin "7") (pinfunction "VCC_IO_7") (pintype "power_in"))
      (node (ref "U10") (pin "8") (pinfunction "VCC_8") (pintype "power_in"))
      (node (ref "U14") (pin "11") (pinfunction "V_BCKP_11") (pintype "passive"))
      (node (ref "U14") (pin "24") (pinfunction "VDD_USB_24") (pintype "passive"))
      (node (ref "U14") (pin "6") (pinfunction "VCC_6") (pintype "passive"))
    )
    (net (code "49") (name "unconnected-(U10-Reserved-Pad13)") (class "Default")
      (node (ref "U10") (pin "13") (pinfunction "Reserved_13") (pintype "passive+no_connect"))
    )
    (net (code "50") (name "unconnected-(U10-~{SAFEBOOT}-Pad18)") (class "Default")
      (node (ref "U10") (pin "18") (pinfunction "~{SAFEBOOT}_18") (pintype "input+no_connect"))
    )
    (net (code "51") (name "unconnected-(U11B-NC-Pad10)") (class "Default")
      (node (ref "U11") (pin "10") (pinfunction "NC_10") (pintype "passive"))
    )
    (net (code "52") (name "unconnected-(U11B-NC-Pad11)") (class "Default")
      (node (ref "U11") (pin "11") (pinfunction "NC_11") (pintype "passive"))
    )
    (net (code "53") (name "unconnected-(U11B-NC-Pad12)") (class "Default")
      (node (ref "U11") (pin "12") (pinfunction "NC_12") (pintype "passive"))
    )
    (net (code "54") (name "unconnected-(U11B-NC-Pad13)") (class "Default")
      (node (ref "U11") (pin "13") (pinfunction "NC_13") (pintype "passive"))
    )
    (net (code "55") (name "unconnected-(U11B-NC-Pad14)") (class "Default")
      (node (ref "U11") (pin "14") (pinfunction "NC_14") (pintype "passive"))
    )
    (net (code "56") (name "unconnected-(U11B-NC-Pad16)") (class "Default")
      (node (ref "U11") (pin "16") (pinfunction "NC_16") (pintype "passive"))
    )
    (net (code "57") (name "unconnected-(U11B-NC-Pad18)") (class "Default")
      (node (ref "U11") (pin "18") (pinfunction "NC_18") (pintype "passive"))
    )
    (net (code "58") (name "unconnected-(U11B-USB_POWER-Pad6)") (class "Default")
      (node (ref "U11") (pin "6") (pinfunction "USB_POWER_6") (pintype "passive"))
    )
    (net (code "59") (name "unconnected-(U13-RIN2+-Pad3)") (class "Default")
      (node (ref "U13") (pin "3") (pinfunction "RIN2+_3") (pintype "input+no_connect"))
    )
    (net (code "60") (name "unconnected-(U13-RIN2--Pad4)") (class "Default")
      (node (ref "U13") (pin "4") (pinfunction "RIN2-_4") (pintype "input+no_connect"))
    )
    (net (code "61") (name "unconnected-(U13-ROUT2-Pad6)") (class "Default")
      (node (ref "U13") (pin "6") (pinfunction "ROUT2_6") (pintype "output+no_connect"))
    )
    (net (code "62") (name "unconnected-(U14-DSEL-Pad5)") (class "Default")
      (node (ref "U14") (pin "5") (pinfunction "DSEL_5") (pintype "passive+no_connect"))
    )
    (net (code "63") (name "unconnected-(U14-SAFEBOOT_N-Pad12)") (class "Default")
      (node (ref "U14") (pin "12") (pinfunction "SAFEBOOT_N_12") (pintype "passive+no_connect"))
    )
    (net (code "64") (name "unconnected-(U14-USB_DM-Pad25)") (class "Default")
      (node (ref "U14") (pin "25") (pinfunction "USB_DM_25") (pintype "passive+no_connect"))
    )
    (net (code "65") (name "unconnected-(U14-USB_DP-Pad26)") (class "Default")
      (node (ref "U14") (pin "26") (pinfunction "USB_DP_26") (pintype "passive+no_connect"))
    )
    (net (code "66") (name "unconnected-(U14-VCC_OUT-Pad8)") (class "Default")
      (node (ref "U14") (pin "8") (pinfunction "VCC_OUT_8") (pintype "passive+no_connect"))
    )
  )
)
